# Orbiter_RING_V4_0.net
KiCad netlist of a schematic drawn in EAGLE
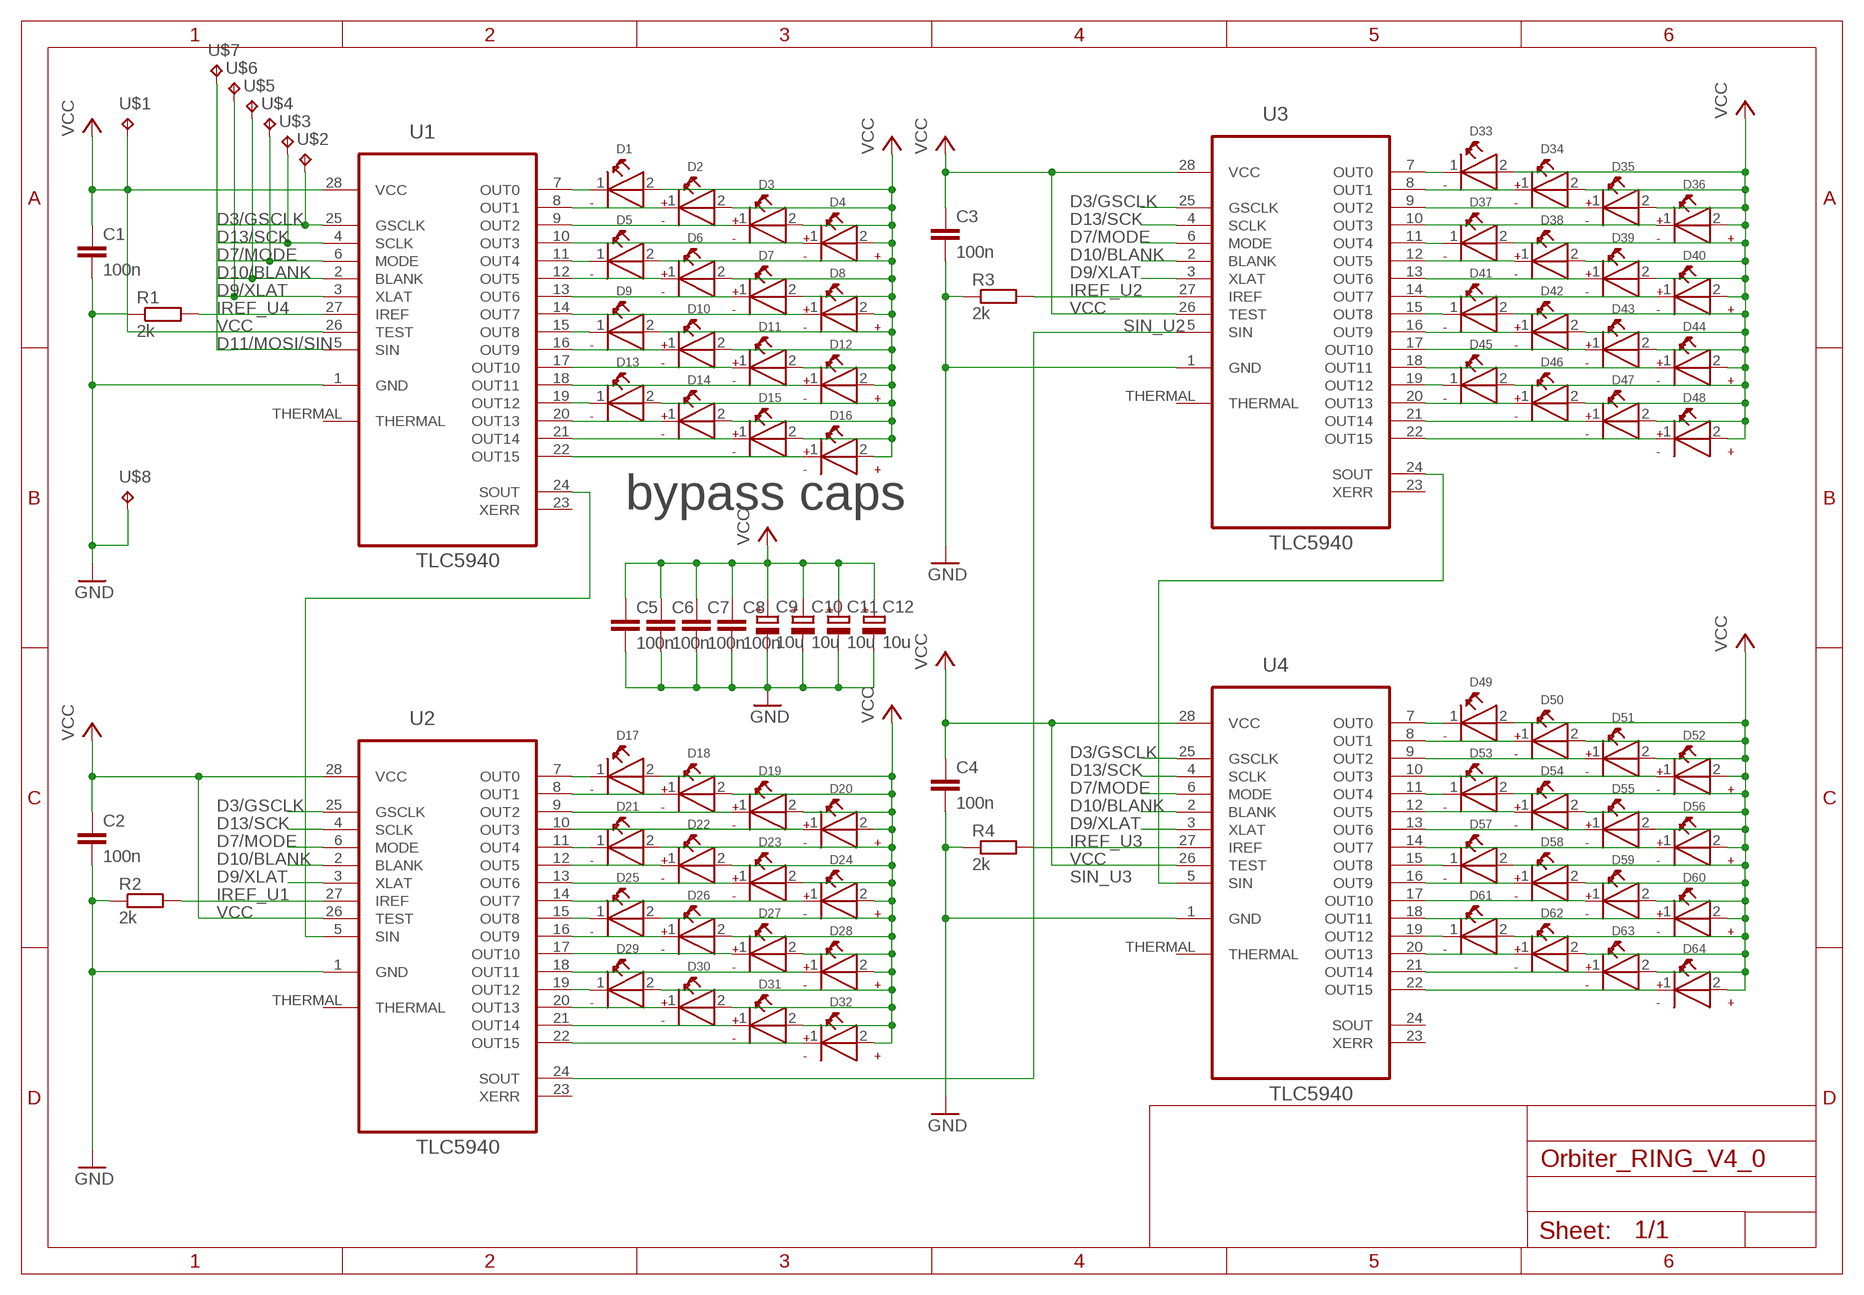
[diagram p0: schematic, sheet 1]

(export (version "E")
  (design (tool "Eeschema 10.0.6"))
  (components
    (comp (ref "C1")
      (value "100n")
      (footprint "eagle-import:C0603")
      (libsource (lib "eagle-import") (part "CAPACITOR{dblquote}"))
    )
    (comp (ref "C2")
      (value "100n")
      (footprint "eagle-import:C0603")
      (libsource (lib "eagle-import") (part "CAPACITOR{dblquote}"))
    )
    (comp (ref "C3")
      (value "100n")
      (footprint "eagle-import:C0603")
      (libsource (lib "eagle-import") (part "CAPACITOR{dblquote}"))
    )
    (comp (ref "C4")
      (value "100n")
      (footprint "eagle-import:C0603")
      (libsource (lib "eagle-import") (part "CAPACITOR{dblquote}"))
    )
    (comp (ref "C5")
      (value "100n")
      (footprint "eagle-import:C0603")
      (libsource (lib "eagle-import") (part "CAPACITOR{dblquote}"))
    )
    (comp (ref "C6")
      (value "100n")
      (footprint "eagle-import:C0603")
      (libsource (lib "eagle-import") (part "CAPACITOR{dblquote}"))
    )
    (comp (ref "C7")
      (value "100n")
      (footprint "eagle-import:C0603")
      (libsource (lib "eagle-import") (part "CAPACITOR{dblquote}"))
    )
    (comp (ref "C8")
      (value "100n")
      (footprint "eagle-import:C0603")
      (libsource (lib "eagle-import") (part "CAPACITOR{dblquote}"))
    )
    (comp (ref "C9")
      (value "10u")
      (footprint "eagle-import:153CLV-0605")
      (libsource (lib "eagle-import") (part "SMD_ELCTROLYTIC"))
    )
    (comp (ref "C10")
      (value "10u")
      (footprint "eagle-import:153CLV-0605")
      (libsource (lib "eagle-import") (part "SMD_ELCTROLYTIC"))
    )
    (comp (ref "C11")
      (value "10u")
      (footprint "eagle-import:153CLV-0605")
      (libsource (lib "eagle-import") (part "SMD_ELCTROLYTIC"))
    )
    (comp (ref "C12")
      (value "10u")
      (footprint "eagle-import:153CLV-0605")
      (libsource (lib "eagle-import") (part "SMD_ELCTROLYTIC"))
    )
    (comp (ref "D1")
      (value "SMD_LED_0603")
      (footprint "eagle-import:WL-SMCW_0603")
      (libsource (lib "eagle-import") (part "SMD_LED_0603"))
    )
    (comp (ref "D2")
      (value "SMD_LED_0603")
      (footprint "eagle-import:WL-SMCW_0603")
      (libsource (lib "eagle-import") (part "SMD_LED_0603"))
    )
    (comp (ref "D3")
      (value "SMD_LED_0603")
      (footprint "eagle-import:WL-SMCW_0603")
      (libsource (lib "eagle-import") (part "SMD_LED_0603"))
    )
    (comp (ref "D4")
      (value "SMD_LED_0603")
      (footprint "eagle-import:WL-SMCW_0603")
      (libsource (lib "eagle-import") (part "SMD_LED_0603"))
    )
    (comp (ref "D5")
      (value "SMD_LED_0603")
      (footprint "eagle-import:WL-SMCW_0603")
      (libsource (lib "eagle-import") (part "SMD_LED_0603"))
    )
    (comp (ref "D6")
      (value "SMD_LED_0603")
      (footprint "eagle-import:WL-SMCW_0603")
      (libsource (lib "eagle-import") (part "SMD_LED_0603"))
    )
    (comp (ref "D7")
      (value "SMD_LED_0603")
      (footprint "eagle-import:WL-SMCW_0603")
      (libsource (lib "eagle-import") (part "SMD_LED_0603"))
    )
    (comp (ref "D8")
      (value "SMD_LED_0603")
      (footprint "eagle-import:WL-SMCW_0603")
      (libsource (lib "eagle-import") (part "SMD_LED_0603"))
    )
    (comp (ref "D9")
      (value "SMD_LED_0603")
      (footprint "eagle-import:WL-SMCW_0603")
      (libsource (lib "eagle-import") (part "SMD_LED_0603"))
    )
    (comp (ref "D10")
      (value "SMD_LED_0603")
      (footprint "eagle-import:WL-SMCW_0603")
      (libsource (lib "eagle-import") (part "SMD_LED_0603"))
    )
    (comp (ref "D11")
      (value "SMD_LED_0603")
      (footprint "eagle-import:WL-SMCW_0603")
      (libsource (lib "eagle-import") (part "SMD_LED_0603"))
    )
    (comp (ref "D12")
      (value "SMD_LED_0603")
      (footprint "eagle-import:WL-SMCW_0603")
      (libsource (lib "eagle-import") (part "SMD_LED_0603"))
    )
    (comp (ref "D13")
      (value "SMD_LED_0603")
      (footprint "eagle-import:WL-SMCW_0603")
      (libsource (lib "eagle-import") (part "SMD_LED_0603"))
    )
    (comp (ref "D14")
      (value "SMD_LED_0603")
      (footprint "eagle-import:WL-SMCW_0603")
      (libsource (lib "eagle-import") (part "SMD_LED_0603"))
    )
    (comp (ref "D15")
      (value "SMD_LED_0603")
      (footprint "eagle-import:WL-SMCW_0603")
      (libsource (lib "eagle-import") (part "SMD_LED_0603"))
    )
    (comp (ref "D16")
      (value "SMD_LED_0603")
      (footprint "eagle-import:WL-SMCW_0603")
      (libsource (lib "eagle-import") (part "SMD_LED_0603"))
    )
    (comp (ref "D17")
      (value "SMD_LED_0603")
      (footprint "eagle-import:WL-SMCW_0603")
      (libsource (lib "eagle-import") (part "SMD_LED_0603"))
    )
    (comp (ref "D18")
      (value "SMD_LED_0603")
      (footprint "eagle-import:WL-SMCW_0603")
      (libsource (lib "eagle-import") (part "SMD_LED_0603"))
    )
    (comp (ref "D19")
      (value "SMD_LED_0603")
      (footprint "eagle-import:WL-SMCW_0603")
      (libsource (lib "eagle-import") (part "SMD_LED_0603"))
    )
    (comp (ref "D20")
      (value "SMD_LED_0603")
      (footprint "eagle-import:WL-SMCW_0603")
      (libsource (lib "eagle-import") (part "SMD_LED_0603"))
    )
    (comp (ref "D21")
      (value "SMD_LED_0603")
      (footprint "eagle-import:WL-SMCW_0603")
      (libsource (lib "eagle-import") (part "SMD_LED_0603"))
    )
    (comp (ref "D22")
      (value "SMD_LED_0603")
      (footprint "eagle-import:WL-SMCW_0603")
      (libsource (lib "eagle-import") (part "SMD_LED_0603"))
    )
    (comp (ref "D23")
      (value "SMD_LED_0603")
      (footprint "eagle-import:WL-SMCW_0603")
      (libsource (lib "eagle-import") (part "SMD_LED_0603"))
    )
    (comp (ref "D24")
      (value "SMD_LED_0603")
      (footprint "eagle-import:WL-SMCW_0603")
      (libsource (lib "eagle-import") (part "SMD_LED_0603"))
    )
    (comp (ref "D25")
      (value "SMD_LED_0603")
      (footprint "eagle-import:WL-SMCW_0603")
      (libsource (lib "eagle-import") (part "SMD_LED_0603"))
    )
    (comp (ref "D26")
      (value "SMD_LED_0603")
      (footprint "eagle-import:WL-SMCW_0603")
      (libsource (lib "eagle-import") (part "SMD_LED_0603"))
    )
    (comp (ref "D27")
      (value "SMD_LED_0603")
      (footprint "eagle-import:WL-SMCW_0603")
      (libsource (lib "eagle-import") (part "SMD_LED_0603"))
    )
    (comp (ref "D28")
      (value "SMD_LED_0603")
      (footprint "eagle-import:WL-SMCW_0603")
      (libsource (lib "eagle-import") (part "SMD_LED_0603"))
    )
    (comp (ref "D29")
      (value "SMD_LED_0603")
      (footprint "eagle-import:WL-SMCW_0603")
      (libsource (lib "eagle-import") (part "SMD_LED_0603"))
    )
    (comp (ref "D30")
      (value "SMD_LED_0603")
      (footprint "eagle-import:WL-SMCW_0603")
      (libsource (lib "eagle-import") (part "SMD_LED_0603"))
    )
    (comp (ref "D31")
      (value "SMD_LED_0603")
      (footprint "eagle-import:WL-SMCW_0603")
      (libsource (lib "eagle-import") (part "SMD_LED_0603"))
    )
    (comp (ref "D32")
      (value "SMD_LED_0603")
      (footprint "eagle-import:WL-SMCW_0603")
      (libsource (lib "eagle-import") (part "SMD_LED_0603"))
    )
    (comp (ref "D33")
      (value "SMD_LED_0603")
      (footprint "eagle-import:WL-SMCW_0603")
      (libsource (lib "eagle-import") (part "SMD_LED_0603"))
    )
    (comp (ref "D34")
      (value "SMD_LED_0603")
      (footprint "eagle-import:WL-SMCW_0603")
      (libsource (lib "eagle-import") (part "SMD_LED_0603"))
    )
    (comp (ref "D35")
      (value "SMD_LED_0603")
      (footprint "eagle-import:WL-SMCW_0603")
      (libsource (lib "eagle-import") (part "SMD_LED_0603"))
    )
    (comp (ref "D36")
      (value "SMD_LED_0603")
      (footprint "eagle-import:WL-SMCW_0603")
      (libsource (lib "eagle-import") (part "SMD_LED_0603"))
    )
    (comp (ref "D37")
      (value "SMD_LED_0603")
      (footprint "eagle-import:WL-SMCW_0603")
      (libsource (lib "eagle-import") (part "SMD_LED_0603"))
    )
    (comp (ref "D38")
      (value "SMD_LED_0603")
      (footprint "eagle-import:WL-SMCW_0603")
      (libsource (lib "eagle-import") (part "SMD_LED_0603"))
    )
    (comp (ref "D39")
      (value "SMD_LED_0603")
      (footprint "eagle-import:WL-SMCW_0603")
      (libsource (lib "eagle-import") (part "SMD_LED_0603"))
    )
    (comp (ref "D40")
      (value "SMD_LED_0603")
      (footprint "eagle-import:WL-SMCW_0603")
      (libsource (lib "eagle-import") (part "SMD_LED_0603"))
    )
    (comp (ref "D41")
      (value "SMD_LED_0603")
      (footprint "eagle-import:WL-SMCW_0603")
      (libsource (lib "eagle-import") (part "SMD_LED_0603"))
    )
    (comp (ref "D42")
      (value "SMD_LED_0603")
      (footprint "eagle-import:WL-SMCW_0603")
      (libsource (lib "eagle-import") (part "SMD_LED_0603"))
    )
    (comp (ref "D43")
      (value "SMD_LED_0603")
      (footprint "eagle-import:WL-SMCW_0603")
      (libsource (lib "eagle-import") (part "SMD_LED_0603"))
    )
    (comp (ref "D44")
      (value "SMD_LED_0603")
      (footprint "eagle-import:WL-SMCW_0603")
      (libsource (lib "eagle-import") (part "SMD_LED_0603"))
    )
    (comp (ref "D45")
      (value "SMD_LED_0603")
      (footprint "eagle-import:WL-SMCW_0603")
      (libsource (lib "eagle-import") (part "SMD_LED_0603"))
    )
    (comp (ref "D46")
      (value "SMD_LED_0603")
      (footprint "eagle-import:WL-SMCW_0603")
      (libsource (lib "eagle-import") (part "SMD_LED_0603"))
    )
    (comp (ref "D47")
      (value "SMD_LED_0603")
      (footprint "eagle-import:WL-SMCW_0603")
      (libsource (lib "eagle-import") (part "SMD_LED_0603"))
    )
    (comp (ref "D48")
      (value "SMD_LED_0603")
      (footprint "eagle-import:WL-SMCW_0603")
      (libsource (lib "eagle-import") (part "SMD_LED_0603"))
    )
    (comp (ref "D49")
      (value "SMD_LED_0603")
      (footprint "eagle-import:WL-SMCW_0603")
      (libsource (lib "eagle-import") (part "SMD_LED_0603"))
    )
    (comp (ref "D50")
      (value "SMD_LED_0603")
      (footprint "eagle-import:WL-SMCW_0603")
      (libsource (lib "eagle-import") (part "SMD_LED_0603"))
    )
    (comp (ref "D51")
      (value "SMD_LED_0603")
      (footprint "eagle-import:WL-SMCW_0603")
      (libsource (lib "eagle-import") (part "SMD_LED_0603"))
    )
    (comp (ref "D52")
      (value "SMD_LED_0603")
      (footprint "eagle-import:WL-SMCW_0603")
      (libsource (lib "eagle-import") (part "SMD_LED_0603"))
    )
    (comp (ref "D53")
      (value "SMD_LED_0603")
      (footprint "eagle-import:WL-SMCW_0603")
      (libsource (lib "eagle-import") (part "SMD_LED_0603"))
    )
    (comp (ref "D54")
      (value "SMD_LED_0603")
      (footprint "eagle-import:WL-SMCW_0603")
      (libsource (lib "eagle-import") (part "SMD_LED_0603"))
    )
    (comp (ref "D55")
      (value "SMD_LED_0603")
      (footprint "eagle-import:WL-SMCW_0603")
      (libsource (lib "eagle-import") (part "SMD_LED_0603"))
    )
    (comp (ref "D56")
      (value "SMD_LED_0603")
      (footprint "eagle-import:WL-SMCW_0603")
      (libsource (lib "eagle-import") (part "SMD_LED_0603"))
    )
    (comp (ref "D57")
      (value "SMD_LED_0603")
      (footprint "eagle-import:WL-SMCW_0603")
      (libsource (lib "eagle-import") (part "SMD_LED_0603"))
    )
    (comp (ref "D58")
      (value "SMD_LED_0603")
      (footprint "eagle-import:WL-SMCW_0603")
      (libsource (lib "eagle-import") (part "SMD_LED_0603"))
    )
    (comp (ref "D59")
      (value "SMD_LED_0603")
      (footprint "eagle-import:WL-SMCW_0603")
      (libsource (lib "eagle-import") (part "SMD_LED_0603"))
    )
    (comp (ref "D60")
      (value "SMD_LED_0603")
      (footprint "eagle-import:WL-SMCW_0603")
      (libsource (lib "eagle-import") (part "SMD_LED_0603"))
    )
    (comp (ref "D61")
      (value "SMD_LED_0603")
      (footprint "eagle-import:WL-SMCW_0603")
      (libsource (lib "eagle-import") (part "SMD_LED_0603"))
    )
    (comp (ref "D62")
      (value "SMD_LED_0603")
      (footprint "eagle-import:WL-SMCW_0603")
      (libsource (lib "eagle-import") (part "SMD_LED_0603"))
    )
    (comp (ref "D63")
      (value "SMD_LED_0603")
      (footprint "eagle-import:WL-SMCW_0603")
      (libsource (lib "eagle-import") (part "SMD_LED_0603"))
    )
    (comp (ref "D64")
      (value "SMD_LED_0603")
      (footprint "eagle-import:WL-SMCW_0603")
      (libsource (lib "eagle-import") (part "SMD_LED_0603"))
    )
    (comp (ref "R1")
      (value "2k")
      (footprint "eagle-import:R0805")
      (libsource (lib "eagle-import") (part "RESISTOR{dblquote}"))
    )
    (comp (ref "R2")
      (value "2k")
      (footprint "eagle-import:R0805")
      (libsource (lib "eagle-import") (part "RESISTOR{dblquote}"))
    )
    (comp (ref "R3")
      (value "2k")
      (footprint "eagle-import:R0805")
      (libsource (lib "eagle-import") (part "RESISTOR{dblquote}"))
    )
    (comp (ref "R4")
      (value "2k")
      (footprint "eagle-import:R0805")
      (libsource (lib "eagle-import") (part "RESISTOR{dblquote}"))
    )
    (comp (ref "U$1")
      (value "TP")
      (footprint "eagle-import:OVAL_PAD")
      (libsource (lib "eagle-import") (part "TP"))
    )
    (comp (ref "U$2")
      (value "TP")
      (footprint "eagle-import:OVAL_PAD")
      (libsource (lib "eagle-import") (part "TP"))
    )
    (comp (ref "U$3")
      (value "TP")
      (footprint "eagle-import:OVAL_PAD")
      (libsource (lib "eagle-import") (part "TP"))
    )
    (comp (ref "U$4")
      (value "TP")
      (footprint "eagle-import:OVAL_PAD")
      (libsource (lib "eagle-import") (part "TP"))
    )
    (comp (ref "U$5")
      (value "TP")
      (footprint "eagle-import:OVAL_PAD")
      (libsource (lib "eagle-import") (part "TP"))
    )
    (comp (ref "U$6")
      (value "TP")
      (footprint "eagle-import:OVAL_PAD")
      (libsource (lib "eagle-import") (part "TP"))
    )
    (comp (ref "U$7")
      (value "TP")
      (footprint "eagle-import:OVAL_PAD")
      (libsource (lib "eagle-import") (part "TP"))
    )
    (comp (ref "U$8")
      (value "TP")
      (footprint "eagle-import:OVAL_PAD")
      (libsource (lib "eagle-import") (part "TP"))
    )
    (comp (ref "U1")
      (value "TLC5940")
      (footprint "eagle-import:SOP65P640X120-29N")
      (fields (field (name "MPN") "TLC59401PWP"))
      (libsource (lib "eagle-import") (part "TLC59401PWP"))
    )
    (comp (ref "U2")
      (value "TLC5940")
      (footprint "eagle-import:SOP65P640X120-29N")
      (fields (field (name "MPN") "TLC59401PWP"))
      (libsource (lib "eagle-import") (part "TLC59401PWP"))
    )
    (comp (ref "U3")
      (value "TLC5940")
      (footprint "eagle-import:SOP65P640X120-29N")
      (fields (field (name "MPN") "TLC59401PWP"))
      (libsource (lib "eagle-import") (part "TLC59401PWP"))
    )
    (comp (ref "U4")
      (value "TLC5940")
      (footprint "eagle-import:SOP65P640X120-29N")
      (fields (field (name "MPN") "TLC59401PWP"))
      (libsource (lib "eagle-import") (part "TLC59401PWP"))
    )
  )
  (nets
    (net (code "1") (name "/D3{slash}GSCLK") (class "Default")
      (node (ref "U$2") (pin "P$1") (pinfunction "TP_P$1") (pintype "input"))
      (node (ref "U1") (pin "25") (pinfunction "GSCLK_25") (pintype "input"))
      (node (ref "U2") (pin "25") (pinfunction "GSCLK_25") (pintype "input"))
      (node (ref "U3") (pin "25") (pinfunction "GSCLK_25") (pintype "input"))
      (node (ref "U4") (pin "25") (pinfunction "GSCLK_25") (pintype "input"))
    )
    (net (code "2") (name "/D7{slash}MODE") (class "Default")
      (node (ref "U$4") (pin "P$1") (pinfunction "TP_P$1") (pintype "input"))
      (node (ref "U1") (pin "6") (pinfunction "MODE_6") (pintype "input"))
      (node (ref "U2") (pin "6") (pinfunction "MODE_6") (pintype "input"))
      (node (ref "U3") (pin "6") (pinfunction "MODE_6") (pintype "input"))
      (node (ref "U4") (pin "6") (pinfunction "MODE_6") (pintype "input"))
    )
    (net (code "3") (name "/D9{slash}XLAT") (class "Default")
      (node (ref "U$6") (pin "P$1") (pinfunction "TP_P$1") (pintype "input"))
      (node (ref "U1") (pin "3") (pinfunction "XLAT_3") (pintype "input"))
      (node (ref "U2") (pin "3") (pinfunction "XLAT_3") (pintype "input"))
      (node (ref "U3") (pin "3") (pinfunction "XLAT_3") (pintype "input"))
      (node (ref "U4") (pin "3") (pinfunction "XLAT_3") (pintype "input"))
    )
    (net (code "4") (name "/D10{slash}BLANK") (class "Default")
      (node (ref "U$5") (pin "P$1") (pinfunction "TP_P$1") (pintype "input"))
      (node (ref "U1") (pin "2") (pinfunction "BLANK_2") (pintype "input"))
      (node (ref "U2") (pin "2") (pinfunction "BLANK_2") (pintype "input"))
      (node (ref "U3") (pin "2") (pinfunction "BLANK_2") (pintype "input"))
      (node (ref "U4") (pin "2") (pinfunction "BLANK_2") (pintype "input"))
    )
    (net (code "5") (name "/D11{slash}MOSI{slash}SIN") (class "Default")
      (node (ref "U$7") (pin "P$1") (pinfunction "TP_P$1") (pintype "input"))
      (node (ref "U1") (pin "5") (pinfunction "SIN_5") (pintype "input"))
    )
    (net (code "6") (name "/D13{slash}SCK") (class "Default")
      (node (ref "U$3") (pin "P$1") (pinfunction "TP_P$1") (pintype "input"))
      (node (ref "U1") (pin "4") (pinfunction "SCLK_4") (pintype "input"))
      (node (ref "U2") (pin "4") (pinfunction "SCLK_4") (pintype "input"))
      (node (ref "U3") (pin "4") (pinfunction "SCLK_4") (pintype "input"))
      (node (ref "U4") (pin "4") (pinfunction "SCLK_4") (pintype "input"))
    )
    (net (code "7") (name "/IREF_U1") (class "Default")
      (node (ref "R2") (pin "2") (pinfunction "2_2") (pintype "passive"))
      (node (ref "U2") (pin "27") (pinfunction "IREF_27") (pintype "input"))
    )
    (net (code "8") (name "/IREF_U2") (class "Default")
      (node (ref "R3") (pin "2") (pinfunction "2_2") (pintype "passive"))
      (node (ref "U3") (pin "27") (pinfunction "IREF_27") (pintype "input"))
    )
    (net (code "9") (name "/IREF_U3") (class "Default")
      (node (ref "R4") (pin "2") (pinfunction "2_2") (pintype "passive"))
      (node (ref "U4") (pin "27") (pinfunction "IREF_27") (pintype "input"))
    )
    (net (code "10") (name "/IREF_U4") (class "Default")
      (node (ref "R1") (pin "2") (pinfunction "2_2") (pintype "passive"))
      (node (ref "U1") (pin "27") (pinfunction "IREF_27") (pintype "input"))
    )
    (net (code "11") (name "/SIN_U2") (class "Default")
      (node (ref "U2") (pin "24") (pinfunction "SOUT_24") (pintype "output"))
      (node (ref "U3") (pin "5") (pinfunction "SIN_5") (pintype "input"))
    )
    (net (code "12") (name "/SIN_U3") (class "Default")
      (node (ref "U3") (pin "24") (pinfunction "SOUT_24") (pintype "output"))
      (node (ref "U4") (pin "5") (pinfunction "SIN_5") (pintype "input"))
    )
    (net (code "13") (name "GND") (class "Default")
      (node (ref "C1") (pin "2") (pinfunction "2_2") (pintype "passive"))
      (node (ref "C10") (pin "-") (pinfunction "-_-") (pintype "passive"))
      (node (ref "C11") (pin "-") (pinfunction "-_-") (pintype "passive"))
      (node (ref "C12") (pin "-") (pinfunction "-_-") (pintype "passive"))
      (node (ref "C2") (pin "2") (pinfunction "2_2") (pintype "passive"))
      (node (ref "C3") (pin "2") (pinfunction "2_2") (pintype "passive"))
      (node (ref "C4") (pin "2") (pinfunction "2_2") (pintype "passive"))
      (node (ref "C5") (pin "2") (pinfunction "2_2") (pintype "passive"))
      (node (ref "C6") (pin "2") (pinfunction "2_2") (pintype "passive"))
      (node (ref "C7") (pin "2") (pinfunction "2_2") (pintype "passive"))
      (node (ref "C8") (pin "2") (pinfunction "2_2") (pintype "passive"))
      (node (ref "C9") (pin "-") (pinfunction "-_-") (pintype "passive"))
      (node (ref "R1") (pin "1") (pinfunction "1_1") (pintype "passive"))
      (node (ref "R2") (pin "1") (pinfunction "1_1") (pintype "passive"))
      (node (ref "R3") (pin "1") (pinfunction "1_1") (pintype "passive"))
      (node (ref "R4") (pin "1") (pinfunction "1_1") (pintype "passive"))
      (node (ref "U$8") (pin "P$1") (pinfunction "TP_P$1") (pintype "input"))
      (node (ref "U1") (pin "1") (pinfunction "GND_1") (pintype "passive"))
      (node (ref "U2") (pin "1") (pinfunction "GND_1") (pintype "passive"))
      (node (ref "U3") (pin "1") (pinfunction "GND_1") (pintype "passive"))
      (node (ref "U4") (pin "1") (pinfunction "GND_1") (pintype "passive"))
    )
    (net (code "14") (name "Net-(D1--)") (class "Default")
      (node (ref "D1") (pin "1") (pinfunction "-_1") (pintype "passive"))
      (node (ref "U1") (pin "7") (pinfunction "OUT0_7") (pintype "output"))
    )
    (net (code "15") (name "Net-(D2--)") (class "Default")
      (node (ref "D2") (pin "1") (pinfunction "-_1") (pintype "passive"))
      (node (ref "U1") (pin "8") (pinfunction "OUT1_8") (pintype "output"))
    )
    (net (code "16") (name "Net-(D3--)") (class "Default")
      (node (ref "D3") (pin "1") (pinfunction "-_1") (pintype "passive"))
      (node (ref "U1") (pin "9") (pinfunction "OUT2_9") (pintype "output"))
    )
    (net (code "17") (name "Net-(D4--)") (class "Default")
      (node (ref "D4") (pin "1") (pinfunction "-_1") (pintype "passive"))
      (node (ref "U1") (pin "10") (pinfunction "OUT3_10") (pintype "output"))
    )
    (net (code "18") (name "Net-(D5--)") (class "Default")
      (node (ref "D5") (pin "1") (pinfunction "-_1") (pintype "passive"))
      (node (ref "U1") (pin "11") (pinfunction "OUT4_11") (pintype "output"))
    )
    (net (code "19") (name "Net-(D6--)") (class "Default")
      (node (ref "D6") (pin "1") (pinfunction "-_1") (pintype "passive"))
      (node (ref "U1") (pin "12") (pinfunction "OUT5_12") (pintype "output"))
    )
    (net (code "20") (name "Net-(D7--)") (class "Default")
      (node (ref "D7") (pin "1") (pinfunction "-_1") (pintype "passive"))
      (node (ref "U1") (pin "13") (pinfunction "OUT6_13") (pintype "output"))
    )
    (net (code "21") (name "Net-(D8--)") (class "Default")
      (node (ref "D8") (pin "1") (pinfunction "-_1") (pintype "passive"))
      (node (ref "U1") (pin "14") (pinfunction "OUT7_14") (pintype "output"))
    )
    (net (code "22") (name "Net-(D9--)") (class "Default")
      (node (ref "D9") (pin "1") (pinfunction "-_1") (pintype "passive"))
      (node (ref "U1") (pin "15") (pinfunction "OUT8_15") (pintype "output"))
    )
    (net (code "23") (name "Net-(D10--)") (class "Default")
      (node (ref "D10") (pin "1") (pinfunction "-_1") (pintype "passive"))
      (node (ref "U1") (pin "16") (pinfunction "OUT9_16") (pintype "output"))
    )
    (net (code "24") (name "Net-(D11--)") (class "Default")
      (node (ref "D11") (pin "1") (pinfunction "-_1") (pintype "passive"))
      (node (ref "U1") (pin "17") (pinfunction "OUT10_17") (pintype "output"))
    )
    (net (code "25") (name "Net-(D12--)") (class "Default")
      (node (ref "D12") (pin "1") (pinfunction "-_1") (pintype "passive"))
      (node (ref "U1") (pin "18") (pinfunction "OUT11_18") (pintype "output"))
    )
    (net (code "26") (name "Net-(D13--)") (class "Default")
      (node (ref "D13") (pin "1") (pinfunction "-_1") (pintype "passive"))
      (node (ref "U1") (pin "19") (pinfunction "OUT12_19") (pintype "output"))
    )
    (net (code "27") (name "Net-(D14--)") (class "Default")
      (node (ref "D14") (pin "1") (pinfunction "-_1") (pintype "passive"))
      (node (ref "U1") (pin "20") (pinfunction "OUT13_20") (pintype "output"))
    )
    (net (code "28") (name "Net-(D15--)") (class "Default")
      (node (ref "D15") (pin "1") (pinfunction "-_1") (pintype "passive"))
      (node (ref "U1") (pin "21") (pinfunction "OUT14_21") (pintype "output"))
    )
    (net (code "29") (name "Net-(D16--)") (class "Default")
      (node (ref "D16") (pin "1") (pinfunction "-_1") (pintype "passive"))
      (node (ref "U1") (pin "22") (pinfunction "OUT15_22") (pintype "output"))
    )
    (net (code "30") (name "Net-(D17--)") (class "Default")
      (node (ref "D17") (pin "1") (pinfunction "-_1") (pintype "passive"))
      (node (ref "U2") (pin "7") (pinfunction "OUT0_7") (pintype "output"))
    )
    (net (code "31") (name "Net-(D18--)") (class "Default")
      (node (ref "D18") (pin "1") (pinfunction "-_1") (pintype "passive"))
      (node (ref "U2") (pin "8") (pinfunction "OUT1_8") (pintype "output"))
    )
    (net (code "32") (name "Net-(D19--)") (class "Default")
      (node (ref "D19") (pin "1") (pinfunction "-_1") (pintype "passive"))
      (node (ref "U2") (pin "9") (pinfunction "OUT2_9") (pintype "output"))
    )
    (net (code "33") (name "Net-(D20--)") (class "Default")
      (node (ref "D20") (pin "1") (pinfunction "-_1") (pintype "passive"))
      (node (ref "U2") (pin "10") (pinfunction "OUT3_10") (pintype "output"))
    )
    (net (code "34") (name "Net-(D21--)") (class "Default")
      (node (ref "D21") (pin "1") (pinfunction "-_1") (pintype "passive"))
      (node (ref "U2") (pin "11") (pinfunction "OUT4_11") (pintype "output"))
    )
    (net (code "35") (name "Net-(D22--)") (class "Default")
      (node (ref "D22") (pin "1") (pinfunction "-_1") (pintype "passive"))
      (node (ref "U2") (pin "12") (pinfunction "OUT5_12") (pintype "output"))
    )
    (net (code "36") (name "Net-(D23--)") (class "Default")
      (node (ref "D23") (pin "1") (pinfunction "-_1") (pintype "passive"))
      (node (ref "U2") (pin "13") (pinfunction "OUT6_13") (pintype "output"))
    )
    (net (code "37") (name "Net-(D24--)") (class "Default")
      (node (ref "D24") (pin "1") (pinfunction "-_1") (pintype "passive"))
      (node (ref "U2") (pin "14") (pinfunction "OUT7_14") (pintype "output"))
    )
    (net (code "38") (name "Net-(D25--)") (class "Default")
      (node (ref "D25") (pin "1") (pinfunction "-_1") (pintype "passive"))
      (node (ref "U2") (pin "15") (pinfunction "OUT8_15") (pintype "output"))
    )
    (net (code "39") (name "Net-(D26--)") (class "Default")
      (node (ref "D26") (pin "1") (pinfunction "-_1") (pintype "passive"))
      (node (ref "U2") (pin "16") (pinfunction "OUT9_16") (pintype "output"))
    )
    (net (code "40") (name "Net-(D27--)") (class "Default")
      (node (ref "D27") (pin "1") (pinfunction "-_1") (pintype "passive"))
      (node (ref "U2") (pin "17") (pinfunction "OUT10_17") (pintype "output"))
    )
    (net (code "41") (name "Net-(D28--)") (class "Default")
      (node (ref "D28") (pin "1") (pinfunction "-_1") (pintype "passive"))
      (node (ref "U2") (pin "18") (pinfunction "OUT11_18") (pintype "output"))
    )
    (net (code "42") (name "Net-(D29--)") (class "Default")
      (node (ref "D29") (pin "1") (pinfunction "-_1") (pintype "passive"))
      (node (ref "U2") (pin "19") (pinfunction "OUT12_19") (pintype "output"))
    )
    (net (code "43") (name "Net-(D30--)") (class "Default")
      (node (ref "D30") (pin "1") (pinfunction "-_1") (pintype "passive"))
      (node (ref "U2") (pin "20") (pinfunction "OUT13_20") (pintype "output"))
    )
    (net (code "44") (name "Net-(D31--)") (class "Default")
      (node (ref "D31") (pin "1") (pinfunction "-_1") (pintype "passive"))
      (node (ref "U2") (pin "21") (pinfunction "OUT14_21") (pintype "output"))
    )
    (net (code "45") (name "Net-(D32--)") (class "Default")
      (node (ref "D32") (pin "1") (pinfunction "-_1") (pintype "passive"))
      (node (ref "U2") (pin "22") (pinfunction "OUT15_22") (pintype "output"))
    )
    (net (code "46") (name "Net-(D33--)") (class "Default")
      (node (ref "D33") (pin "1") (pinfunction "-_1") (pintype "passive"))
      (node (ref "U3") (pin "7") (pinfunction "OUT0_7") (pintype "output"))
    )
    (net (code "47") (name "Net-(D34--)") (class "Default")
      (node (ref "D34") (pin "1") (pinfunction "-_1") (pintype "passive"))
      (node (ref "U3") (pin "8") (pinfunction "OUT1_8") (pintype "output"))
    )
    (net (code "48") (name "Net-(D35--)") (class "Default")
      (node (ref "D35") (pin "1") (pinfunction "-_1") (pintype "passive"))
      (node (ref "U3") (pin "9") (pinfunction "OUT2_9") (pintype "output"))
    )
    (net (code "49") (name "Net-(D36--)") (class "Default")
      (node (ref "D36") (pin "1") (pinfunction "-_1") (pintype "passive"))
      (node (ref "U3") (pin "10") (pinfunction "OUT3_10") (pintype "output"))
    )
    (net (code "50") (name "Net-(D37--)") (class "Default")
      (node (ref "D37") (pin "1") (pinfunction "-_1") (pintype "passive"))
      (node (ref "U3") (pin "11") (pinfunction "OUT4_11") (pintype "output"))
    )
    (net (code "51") (name "Net-(D38--)") (class "Default")
      (node (ref "D38") (pin "1") (pinfunction "-_1") (pintype "passive"))
      (node (ref "U3") (pin "12") (pinfunction "OUT5_12") (pintype "output"))
    )
    (net (code "52") (name "Net-(D39--)") (class "Default")
      (node (ref "D39") (pin "1") (pinfunction "-_1") (pintype "passive"))
      (node (ref "U3") (pin "13") (pinfunction "OUT6_13") (pintype "output"))
    )
    (net (code "53") (name "Net-(D40--)") (class "Default")
      (node (ref "D40") (pin "1") (pinfunction "-_1") (pintype "passive"))
      (node (ref "U3") (pin "14") (pinfunction "OUT7_14") (pintype "output"))
    )
    (net (code "54") (name "Net-(D41--)") (class "Default")
      (node (ref "D41") (pin "1") (pinfunction "-_1") (pintype "passive"))
      (node (ref "U3") (pin "15") (pinfunction "OUT8_15") (pintype "output"))
    )
    (net (code "55") (name "Net-(D42--)") (class "Default")
      (node (ref "D42") (pin "1") (pinfunction "-_1") (pintype "passive"))
      (node (ref "U3") (pin "16") (pinfunction "OUT9_16") (pintype "output"))
    )
    (net (code "56") (name "Net-(D43--)") (class "Default")
      (node (ref "D43") (pin "1") (pinfunction "-_1") (pintype "passive"))
      (node (ref "U3") (pin "17") (pinfunction "OUT10_17") (pintype "output"))
    )
    (net (code "57") (name "Net-(D44--)") (class "Default")
      (node (ref "D44") (pin "1") (pinfunction "-_1") (pintype "passive"))
      (node (ref "U3") (pin "18") (pinfunction "OUT11_18") (pintype "output"))
    )
    (net (code "58") (name "Net-(D45--)") (class "Default")
      (node (ref "D45") (pin "1") (pinfunction "-_1") (pintype "passive"))
      (node (ref "U3") (pin "19") (pinfunction "OUT12_19") (pintype "output"))
    )
    (net (code "59") (name "Net-(D46--)") (class "Default")
      (node (ref "D46") (pin "1") (pinfunction "-_1") (pintype "passive"))
      (node (ref "U3") (pin "20") (pinfunction "OUT13_20") (pintype "output"))
    )
    (net (code "60") (name "Net-(D47--)") (class "Default")
      (node (ref "D47") (pin "1") (pinfunction "-_1") (pintype "passive"))
      (node (ref "U3") (pin "21") (pinfunction "OUT14_21") (pintype "output"))
    )
    (net (code "61") (name "Net-(D48--)") (class "Default")
      (node (ref "D48") (pin "1") (pinfunction "-_1") (pintype "passive"))
      (node (ref "U3") (pin "22") (pinfunction "OUT15_22") (pintype "output"))
    )
    (net (code "62") (name "Net-(D49--)") (class "Default")
      (node (ref "D49") (pin "1") (pinfunction "-_1") (pintype "passive"))
      (node (ref "U4") (pin "7") (pinfunction "OUT0_7") (pintype "output"))
    )
    (net (code "63") (name "Net-(D50--)") (class "Default")
      (node (ref "D50") (pin "1") (pinfunction "-_1") (pintype "passive"))
      (node (ref "U4") (pin "8") (pinfunction "OUT1_8") (pintype "output"))
    )
    (net (code "64") (name "Net-(D51--)") (class "Default")
      (node (ref "D51") (pin "1") (pinfunction "-_1") (pintype "passive"))
      (node (ref "U4") (pin "9") (pinfunction "OUT2_9") (pintype "output"))
    )
    (net (code "65") (name "Net-(D52--)") (class "Default")
      (node (ref "D52") (pin "1") (pinfunction "-_1") (pintype "passive"))
      (node (ref "U4") (pin "10") (pinfunction "OUT3_10") (pintype "output"))
    )
    (net (code "66") (name "Net-(D53--)") (class "Default")
      (node (ref "D53") (pin "1") (pinfunction "-_1") (pintype "passive"))
      (node (ref "U4") (pin "11") (pinfunction "OUT4_11") (pintype "output"))
    )
    (net (code "67") (name "Net-(D54--)") (class "Default")
      (node (ref "D54") (pin "1") (pinfunction "-_1") (pintype "passive"))
      (node (ref "U4") (pin "12") (pinfunction "OUT5_12") (pintype "output"))
    )
    (net (code "68") (name "Net-(D55--)") (class "Default")
      (node (ref "D55") (pin "1") (pinfunction "-_1") (pintype "passive"))
      (node (ref "U4") (pin "13") (pinfunction "OUT6_13") (pintype "output"))
    )
    (net (code "69") (name "Net-(D56--)") (class "Default")
      (node (ref "D56") (pin "1") (pinfunction "-_1") (pintype "passive"))
      (node (ref "U4") (pin "14") (pinfunction "OUT7_14") (pintype "output"))
    )
    (net (code "70") (name "Net-(D57--)") (class "Default")
      (node (ref "D57") (pin "1") (pinfunction "-_1") (pintype "passive"))
      (node (ref "U4") (pin "15") (pinfunction "OUT8_15") (pintype "output"))
    )
    (net (code "71") (name "Net-(D58--)") (class "Default")
      (node (ref "D58") (pin "1") (pinfunction "-_1") (pintype "passive"))
      (node (ref "U4") (pin "16") (pinfunction "OUT9_16") (pintype "output"))
    )
    (net (code "72") (name "Net-(D59--)") (class "Default")
      (node (ref "D59") (pin "1") (pinfunction "-_1") (pintype "passive"))
      (node (ref "U4") (pin "17") (pinfunction "OUT10_17") (pintype "output"))
    )
    (net (code "73") (name "Net-(D60--)") (class "Default")
      (node (ref "D60") (pin "1") (pinfunction "-_1") (pintype "passive"))
      (node (ref "U4") (pin "18") (pinfunction "OUT11_18") (pintype "output"))
    )
    (net (code "74") (name "Net-(D61--)") (class "Default")
      (node (ref "D61") (pin "1") (pinfunction "-_1") (pintype "passive"))
      (node (ref "U4") (pin "19") (pinfunction "OUT12_19") (pintype "output"))
    )
    (net (code "75") (name "Net-(D62--)") (class "Default")
      (node (ref "D62") (pin "1") (pinfunction "-_1") (pintype "passive"))
      (node (ref "U4") (pin "20") (pinfunction "OUT13_20") (pintype "output"))
    )
    (net (code "76") (name "Net-(D63--)") (class "Default")
      (node (ref "D63") (pin "1") (pinfunction "-_1") (pintype "passive"))
      (node (ref "U4") (pin "21") (pinfunction "OUT14_21") (pintype "output"))
    )
    (net (code "77") (name "Net-(D64--)") (class "Default")
      (node (ref "D64") (pin "1") (pinfunction "-_1") (pintype "passive"))
      (node (ref "U4") (pin "22") (pinfunction "OUT15_22") (pintype "output"))
    )
    (net (code "78") (name "Net-(U1-SOUT)") (class "Default")
      (node (ref "U1") (pin "24") (pinfunction "SOUT_24") (pintype "output"))
      (node (ref "U2") (pin "5") (pinfunction "SIN_5") (pintype "input"))
    )
    (net (code "79") (name "VCC") (class "Default")
      (node (ref "C1") (pin "1") (pinfunction "1_1") (pintype "passive"))
      (node (ref "C10") (pin "+") (pinfunction "+_+") (pintype "passive"))
      (node (ref "C11") (pin "+") (pinfunction "+_+") (pintype "passive"))
      (node (ref "C12") (pin "+") (pinfunction "+_+") (pintype "passive"))
      (node (ref "C2") (pin "1") (pinfunction "1_1") (pintype "passive"))
      (node (ref "C3") (pin "1") (pinfunction "1_1") (pintype "passive"))
      (node (ref "C4") (pin "1") (pinfunction "1_1") (pintype "passive"))
      (node (ref "C5") (pin "1") (pinfunction "1_1") (pintype "passive"))
      (node (ref "C6") (pin "1") (pinfunction "1_1") (pintype "passive"))
      (node (ref "C7") (pin "1") (pinfunction "1_1") (pintype "passive"))
      (node (ref "C8") (pin "1") (pinfunction "1_1") (pintype "passive"))
      (node (ref "C9") (pin "+") (pinfunction "+_+") (pintype "passive"))
      (node (ref "D1") (pin "2") (pinfunction "+_2") (pintype "passive"))
      (node (ref "D10") (pin "2") (pinfunction "+_2") (pintype "passive"))
      (node (ref "D11") (pin "2") (pinfunction "+_2") (pintype "passive"))
      (node (ref "D12") (pin "2") (pinfunction "+_2") (pintype "passive"))
      (node (ref "D13") (pin "2") (pinfunction "+_2") (pintype "passive"))
      (node (ref "D14") (pin "2") (pinfunction "+_2") (pintype "passive"))
      (node (ref "D15") (pin "2") (pinfunction "+_2") (pintype "passive"))
      (node (ref "D16") (pin "2") (pinfunction "+_2") (pintype "passive"))
      (node (ref "D17") (pin "2") (pinfunction "+_2") (pintype "passive"))
      (node (ref "D18") (pin "2") (pinfunction "+_2") (pintype "passive"))
      (node (ref "D19") (pin "2") (pinfunction "+_2") (pintype "passive"))
      (node (ref "D2") (pin "2") (pinfunction "+_2") (pintype "passive"))
      (node (ref "D20") (pin "2") (pinfunction "+_2") (pintype "passive"))
      (node (ref "D21") (pin "2") (pinfunction "+_2") (pintype "passive"))
      (node (ref "D22") (pin "2") (pinfunction "+_2") (pintype "passive"))
      (node (ref "D23") (pin "2") (pinfunction "+_2") (pintype "passive"))
      (node (ref "D24") (pin "2") (pinfunction "+_2") (pintype "passive"))
      (node (ref "D25") (pin "2") (pinfunction "+_2") (pintype "passive"))
      (node (ref "D26") (pin "2") (pinfunction "+_2") (pintype "passive"))
      (node (ref "D27") (pin "2") (pinfunction "+_2") (pintype "passive"))
      (node (ref "D28") (pin "2") (pinfunction "+_2") (pintype "passive"))
      (node (ref "D29") (pin "2") (pinfunction "+_2") (pintype "passive"))
      (node (ref "D3") (pin "2") (pinfunction "+_2") (pintype "passive"))
      (node (ref "D30") (pin "2") (pinfunction "+_2") (pintype "passive"))
      (node (ref "D31") (pin "2") (pinfunction "+_2") (pintype "passive"))
      (node (ref "D32") (pin "2") (pinfunction "+_2") (pintype "passive"))
      (node (ref "D33") (pin "2") (pinfunction "+_2") (pintype "passive"))
      (node (ref "D34") (pin "2") (pinfunction "+_2") (pintype "passive"))
      (node (ref "D35") (pin "2") (pinfunction "+_2") (pintype "passive"))
      (node (ref "D36") (pin "2") (pinfunction "+_2") (pintype "passive"))
      (node (ref "D37") (pin "2") (pinfunction "+_2") (pintype "passive"))
      (node (ref "D38") (pin "2") (pinfunction "+_2") (pintype "passive"))
      (node (ref "D39") (pin "2") (pinfunction "+_2") (pintype "passive"))
      (node (ref "D4") (pin "2") (pinfunction "+_2") (pintype "passive"))
      (node (ref "D40") (pin "2") (pinfunction "+_2") (pintype "passive"))
      (node (ref "D41") (pin "2") (pinfunction "+_2") (pintype "passive"))
      (node (ref "D42") (pin "2") (pinfunction "+_2") (pintype "passive"))
      (node (ref "D43") (pin "2") (pinfunction "+_2") (pintype "passive"))
      (node (ref "D44") (pin "2") (pinfunction "+_2") (pintype "passive"))
      (node (ref "D45") (pin "2") (pinfunction "+_2") (pintype "passive"))
      (node (ref "D46") (pin "2") (pinfunction "+_2") (pintype "passive"))
      (node (ref "D47") (pin "2") (pinfunction "+_2") (pintype "passive"))
      (node (ref "D48") (pin "2") (pinfunction "+_2") (pintype "passive"))
      (node (ref "D49") (pin "2") (pinfunction "+_2") (pintype "passive"))
      (node (ref "D5") (pin "2") (pinfunction "+_2") (pintype "passive"))
      (node (ref "D50") (pin "2") (pinfunction "+_2") (pintype "passive"))
      (node (ref "D51") (pin "2") (pinfunction "+_2") (pintype "passive"))
      (node (ref "D52") (pin "2") (pinfunction "+_2") (pintype "passive"))
      (node (ref "D53") (pin "2") (pinfunction "+_2") (pintype "passive"))
      (node (ref "D54") (pin "2") (pinfunction "+_2") (pintype "passive"))
      (node (ref "D55") (pin "2") (pinfunction "+_2") (pintype "passive"))
      (node (ref "D56") (pin "2") (pinfunction "+_2") (pintype "passive"))
      (node (ref "D57") (pin "2") (pinfunction "+_2") (pintype "passive"))
      (node (ref "D58") (pin "2") (pinfunction "+_2") (pintype "passive"))
      (node (ref "D59") (pin "2") (pinfunction "+_2") (pintype "passive"))
      (node (ref "D6") (pin "2") (pinfunction "+_2") (pintype "passive"))
      (node (ref "D60") (pin "2") (pinfunction "+_2") (pintype "passive"))
      (node (ref "D61") (pin "2") (pinfunction "+_2") (pintype "passive"))
      (node (ref "D62") (pin "2") (pinfunction "+_2") (pintype "passive"))
      (node (ref "D63") (pin "2") (pinfunction "+_2") (pintype "passive"))
      (node (ref "D64") (pin "2") (pinfunction "+_2") (pintype "passive"))
      (node (ref "D7") (pin "2") (pinfunction "+_2") (pintype "passive"))
      (node (ref "D8") (pin "2") (pinfunction "+_2") (pintype "passive"))
      (node (ref "D9") (pin "2") (pinfunction "+_2") (pintype "passive"))
      (node (ref "U$1") (pin "P$1") (pinfunction "TP_P$1") (pintype "input"))
      (node (ref "U1") (pin "26") (pinfunction "TEST_26") (pintype "input"))
      (node (ref "U1") (pin "28") (pinfunction "VCC_28") (pintype "power_in"))
      (node (ref "U2") (pin "26") (pinfunction "TEST_26") (pintype "input"))
      (node (ref "U2") (pin "28") (pinfunction "VCC_28") (pintype "power_in"))
      (node (ref "U3") (pin "26") (pinfunction "TEST_26") (pintype "input"))
      (node (ref "U3") (pin "28") (pinfunction "VCC_28") (pintype "power_in"))
      (node (ref "U4") (pin "26") (pinfunction "TEST_26") (pintype "input"))
      (node (ref "U4") (pin "28") (pinfunction "VCC_28") (pintype "power_in"))
    )
    (net (code "80") (name "unconnected-(U1-PadTHERMAL)") (class "Default")
      (node (ref "U1") (pin "THERMAL") (pinfunction "THERMAL_THERMAL") (pintype "passive"))
    )
    (net (code "81") (name "unconnected-(U1-XERR-Pad23)") (class "Default")
      (node (ref "U1") (pin "23") (pinfunction "XERR_23") (pintype "output"))
    )
    (net (code "82") (name "unconnected-(U2-PadTHERMAL)") (class "Default")
      (node (ref "U2") (pin "THERMAL") (pinfunction "THERMAL_THERMAL") (pintype "passive"))
    )
    (net (code "83") (name "unconnected-(U2-XERR-Pad23)") (class "Default")
      (node (ref "U2") (pin "23") (pinfunction "XERR_23") (pintype "output"))
    )
    (net (code "84") (name "unconnected-(U3-PadTHERMAL)") (class "Default")
      (node (ref "U3") (pin "THERMAL") (pinfunction "THERMAL_THERMAL") (pintype "passive"))
    )
    (net (code "85") (name "unconnected-(U3-XERR-Pad23)") (class "Default")
      (node (ref "U3") (pin "23") (pinfunction "XERR_23") (pintype "output"))
    )
    (net (code "86") (name "unconnected-(U4-PadTHERMAL)") (class "Default")
      (node (ref "U4") (pin "THERMAL") (pinfunction "THERMAL_THERMAL") (pintype "passive"))
    )
    (net (code "87") (name "unconnected-(U4-SOUT-Pad24)") (class "Default")
      (node (ref "U4") (pin "24") (pinfunction "SOUT_24") (pintype "output"))
    )
    (net (code "88") (name "unconnected-(U4-XERR-Pad23)") (class "Default")
      (node (ref "U4") (pin "23") (pinfunction "XERR_23") (pintype "output"))
    )
  )
)
